# PoE_Injector.net
KiCad netlist of a schematic drawn in Altium Designer
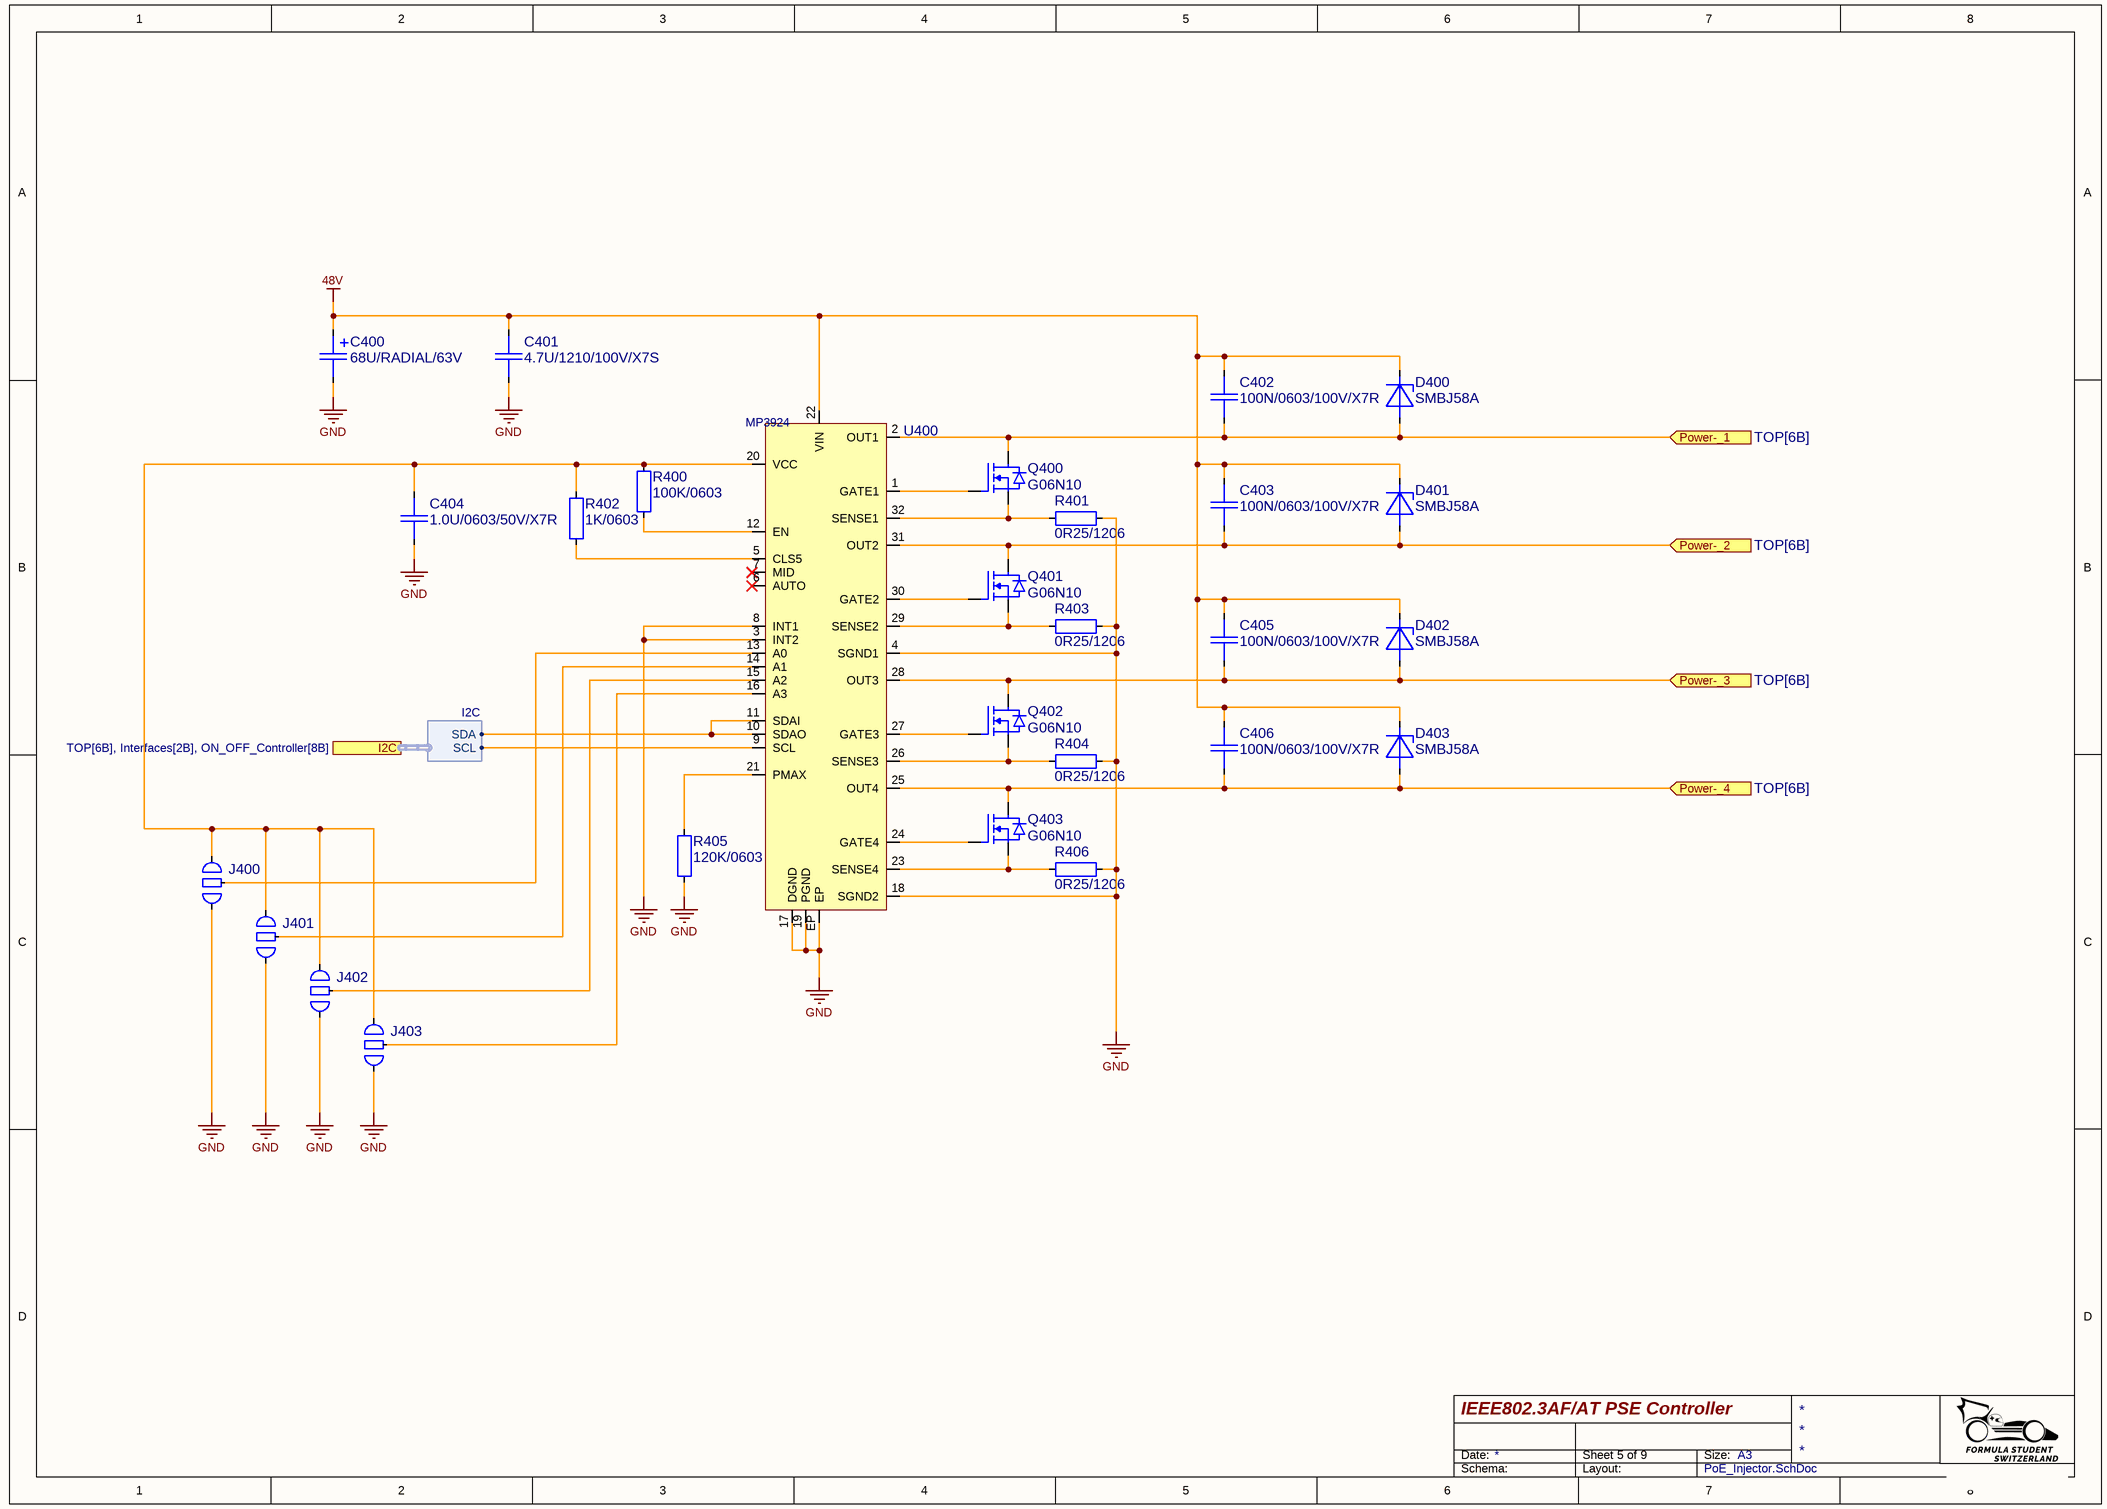
[diagram p0: PoE_Injector.SchDoc]

(export (version "E")
  (design (tool "Eeschema 10.0.6"))
  (components
    (comp (ref "C400")
      (value "68U/RADIAL/63V")
      (footprint "CAP350P80X130")
      (description "CAP THT 8C130 68UF ELKO 63V")
      (fields (field (name "MANUFACTURER") "GENERIC"))
      (libsource (lib "daniw_altium_lib") (part "C_ELEC"))
    )
    (comp (ref "C401")
      (value "4.7U/1210/100V/X7S")
      (footprint "CAP1210_X7R")
      (description "CAP SM 1210 4.7uF 100V X7S")
      (fields (field (name "MANUFACTURER") "GENERIC"))
      (libsource (lib "daniw_altium_lib") (part "C"))
    )
    (comp (ref "C402")
      (value "100N/0603/100V/X7R")
      (footprint "CAP0603_X7R")
      (description "CAP SM 0603 100nF 100V X7R")
      (fields (field (name "MANUFACTURER") "GENERIC"))
      (libsource (lib "daniw_altium_lib") (part "C"))
    )
    (comp (ref "C403")
      (value "100N/0603/100V/X7R")
      (footprint "CAP0603_X7R")
      (description "CAP SM 0603 100nF 100V X7R")
      (fields (field (name "MANUFACTURER") "GENERIC"))
      (libsource (lib "daniw_altium_lib") (part "C"))
    )
    (comp (ref "C404")
      (value "1.0U/0603/50V/X7R")
      (footprint "CAP0603_X7R")
      (description "CAP SM 0603 1.0uF 50V X7R")
      (fields (field (name "MANUFACTURER") "GENERIC"))
      (libsource (lib "daniw_altium_lib") (part "C"))
    )
    (comp (ref "C405")
      (value "100N/0603/100V/X7R")
      (footprint "CAP0603_X7R")
      (description "CAP SM 0603 100nF 100V X7R")
      (fields (field (name "MANUFACTURER") "GENERIC"))
      (libsource (lib "daniw_altium_lib") (part "C"))
    )
    (comp (ref "C406")
      (value "100N/0603/100V/X7R")
      (footprint "CAP0603_X7R")
      (description "CAP SM 0603 100nF 100V X7R")
      (fields (field (name "MANUFACTURER") "GENERIC"))
      (libsource (lib "daniw_altium_lib") (part "C"))
    )
    (comp (ref "D400")
      (value "SMBJ58A")
      (footprint "DIOM5436X265")
      (description "TVS DIODE 58VWM 93.6VC DO214AA")
      (fields (field (name "MANUFACTURER") "Littelfuse Inc."))
      (libsource (lib "daniw_altium_lib") (part "D_Zener"))
    )
    (comp (ref "D401")
      (value "SMBJ58A")
      (footprint "DIOM5436X265")
      (description "TVS DIODE 58VWM 93.6VC DO214AA")
      (fields (field (name "MANUFACTURER") "Littelfuse Inc."))
      (libsource (lib "daniw_altium_lib") (part "D_Zener"))
    )
    (comp (ref "D402")
      (value "SMBJ58A")
      (footprint "DIOM5436X265")
      (description "TVS DIODE 58VWM 93.6VC DO214AA")
      (fields (field (name "MANUFACTURER") "Littelfuse Inc."))
      (libsource (lib "daniw_altium_lib") (part "D_Zener"))
    )
    (comp (ref "D403")
      (value "SMBJ58A")
      (footprint "DIOM5436X265")
      (description "TVS DIODE 58VWM 93.6VC DO214AA")
      (fields (field (name "MANUFACTURER") "Littelfuse Inc."))
      (libsource (lib "daniw_altium_lib") (part "D_Zener"))
    )
    (comp (ref "J400")
      (value "Solder Jumper 3pin 0.2mm")
      (footprint "Solder_Jumper_3pin_0.2mm")
      (description "Solder jumper with three pins with a spacing of 0.2mm")
      (fields (field (name "PART NUMBER") "Solder_Jumper_3pin_0.2mm") (field (name "MANUFACTURER") "NONE"))
      (libsource (lib "daniw_altium_lib") (part "SolderJumper_3"))
    )
    (comp (ref "J401")
      (value "Solder Jumper 3pin 0.2mm")
      (footprint "Solder_Jumper_3pin_0.2mm")
      (description "Solder jumper with three pins with a spacing of 0.2mm")
      (fields (field (name "PART NUMBER") "Solder_Jumper_3pin_0.2mm") (field (name "MANUFACTURER") "NONE"))
      (libsource (lib "daniw_altium_lib") (part "SolderJumper_3"))
    )
    (comp (ref "J402")
      (value "Solder Jumper 3pin 0.2mm")
      (footprint "Solder_Jumper_3pin_0.2mm")
      (description "Solder jumper with three pins with a spacing of 0.2mm")
      (fields (field (name "PART NUMBER") "Solder_Jumper_3pin_0.2mm") (field (name "MANUFACTURER") "NONE"))
      (libsource (lib "daniw_altium_lib") (part "SolderJumper_3"))
    )
    (comp (ref "J403")
      (value "Solder Jumper 3pin 0.2mm")
      (footprint "Solder_Jumper_3pin_0.2mm")
      (description "Solder jumper with three pins with a spacing of 0.2mm")
      (fields (field (name "PART NUMBER") "Solder_Jumper_3pin_0.2mm") (field (name "MANUFACTURER") "NONE"))
      (libsource (lib "daniw_altium_lib") (part "SolderJumper_3"))
    )
    (comp (ref "Q400")
      (value "G06N10")
      (footprint "TO228P990X229-3")
      (description "N100V,RD(MAX)<240M@10V,VTH1.2V~3")
      (fields (field (name "MANUFACTURER") "Goford"))
      (libsource (lib "daniw_altium_lib") (part "MOSFET N_SOT23"))
    )
    (comp (ref "Q401")
      (value "G06N10")
      (footprint "TO228P990X229-3")
      (description "N100V,RD(MAX)<240M@10V,VTH1.2V~3")
      (fields (field (name "MANUFACTURER") "Goford"))
      (libsource (lib "daniw_altium_lib") (part "MOSFET N_SOT23"))
    )
    (comp (ref "Q402")
      (value "G06N10")
      (footprint "TO228P990X229-3")
      (description "N100V,RD(MAX)<240M@10V,VTH1.2V~3")
      (fields (field (name "MANUFACTURER") "Goford"))
      (libsource (lib "daniw_altium_lib") (part "MOSFET N_SOT23"))
    )
    (comp (ref "Q403")
      (value "G06N10")
      (footprint "TO228P990X229-3")
      (description "N100V,RD(MAX)<240M@10V,VTH1.2V~3")
      (fields (field (name "MANUFACTURER") "Goford"))
      (libsource (lib "daniw_altium_lib") (part "MOSFET N_SOT23"))
    )
    (comp (ref "R400")
      (value "100K/0603")
      (footprint "R0603-0.40-WW")
      (description "RES SM 0603 100K")
      (fields (field (name "MANUFACTURER") "GENERIC"))
      (libsource (lib "daniw_altium_lib") (part "R"))
    )
    (comp (ref "R401")
      (value "0R25/1206")
      (footprint "R1206-0.80-WW")
      (description "RES SM 1206 0R25")
      (fields (field (name "MANUFACTURER") "GENERIC"))
      (libsource (lib "daniw_altium_lib") (part "R"))
    )
    (comp (ref "R402")
      (value "1K/0603")
      (footprint "R0603-0.40-WW")
      (description "RES SM 0603 1K")
      (fields (field (name "MANUFACTURER") "GENERIC"))
      (libsource (lib "daniw_altium_lib") (part "R"))
    )
    (comp (ref "R403")
      (value "0R25/1206")
      (footprint "R1206-0.80-WW")
      (description "RES SM 1206 0R25")
      (fields (field (name "MANUFACTURER") "GENERIC"))
      (libsource (lib "daniw_altium_lib") (part "R"))
    )
    (comp (ref "R404")
      (value "0R25/1206")
      (footprint "R1206-0.80-WW")
      (description "RES SM 1206 0R25")
      (fields (field (name "MANUFACTURER") "GENERIC"))
      (libsource (lib "daniw_altium_lib") (part "R"))
    )
    (comp (ref "R405")
      (value "120K/0603")
      (footprint "R0603-0.40-WW")
      (description "RES SM 0603 120K")
      (fields (field (name "MANUFACTURER") "GENERIC"))
      (libsource (lib "daniw_altium_lib") (part "R"))
    )
    (comp (ref "R406")
      (value "0R25/1206")
      (footprint "R1206-0.80-WW")
      (description "RES SM 1206 0R25")
      (fields (field (name "MANUFACTURER") "GENERIC"))
      (libsource (lib "daniw_altium_lib") (part "R"))
    )
    (comp (ref "U400")
      (value "MP3924")
      (footprint "QFN050P500X500X100-32-TH360X360")
      (description "Quad-Port, IEEE 802.3af/at PSE Controller for Power over Ethernet")
      (fields (field (name "MANUFACTURER") "MPS"))
      (libsource (lib "daniw_altium_lib") (part "MP3924"))
    )
  )
  (nets
    (net (code "2") (name "/Power-_1") (class "Default")
      (node (ref "C402") (pin "2") (pinfunction "2_2") (pintype "passive"))
      (node (ref "D400") (pin "2") (pinfunction "2_2") (pintype "passive"))
      (node (ref "Q400") (pin "3") (pinfunction "DRAIN_3") (pintype "passive"))
      (node (ref "U400") (pin "2") (pinfunction "OUT1_2") (pintype "passive"))
    )
    (net (code "3") (name "/Power-_2") (class "Default")
      (node (ref "C403") (pin "2") (pinfunction "2_2") (pintype "passive"))
      (node (ref "D401") (pin "2") (pinfunction "2_2") (pintype "passive"))
      (node (ref "Q401") (pin "3") (pinfunction "DRAIN_3") (pintype "passive"))
      (node (ref "U400") (pin "31") (pinfunction "OUT2_31") (pintype "passive"))
    )
    (net (code "4") (name "/Power-_3") (class "Default")
      (node (ref "C405") (pin "2") (pinfunction "2_2") (pintype "passive"))
      (node (ref "D402") (pin "2") (pinfunction "2_2") (pintype "passive"))
      (node (ref "Q402") (pin "3") (pinfunction "DRAIN_3") (pintype "passive"))
      (node (ref "U400") (pin "28") (pinfunction "OUT3_28") (pintype "passive"))
    )
    (net (code "5") (name "/Power-_4") (class "Default")
      (node (ref "C406") (pin "2") (pinfunction "2_2") (pintype "passive"))
      (node (ref "D403") (pin "2") (pinfunction "2_2") (pintype "passive"))
      (node (ref "Q403") (pin "3") (pinfunction "DRAIN_3") (pintype "passive"))
      (node (ref "U400") (pin "25") (pinfunction "OUT4_25") (pintype "passive"))
    )
    (net (code "6") (name "/SCL") (class "Default")
      (node (ref "U400") (pin "9") (pinfunction "SCL_9") (pintype "passive"))
    )
    (net (code "7") (name "/SDA") (class "Default")
      (node (ref "U400") (pin "10") (pinfunction "SDAO_10") (pintype "passive"))
      (node (ref "U400") (pin "11") (pinfunction "SDAI_11") (pintype "passive"))
    )
    (net (code "9") (name "48V") (class "Default")
      (node (ref "C400") (pin "1") (pinfunction "1_1") (pintype "passive"))
      (node (ref "C401") (pin "1") (pinfunction "1_1") (pintype "passive"))
      (node (ref "C402") (pin "1") (pinfunction "1_1") (pintype "passive"))
      (node (ref "C403") (pin "1") (pinfunction "1_1") (pintype "passive"))
      (node (ref "C405") (pin "1") (pinfunction "1_1") (pintype "passive"))
      (node (ref "C406") (pin "1") (pinfunction "1_1") (pintype "passive"))
      (node (ref "D400") (pin "1") (pinfunction "1_1") (pintype "passive"))
      (node (ref "D401") (pin "1") (pinfunction "1_1") (pintype "passive"))
      (node (ref "D402") (pin "1") (pinfunction "1_1") (pintype "passive"))
      (node (ref "D403") (pin "1") (pinfunction "1_1") (pintype "passive"))
      (node (ref "U400") (pin "22") (pinfunction "VIN_22") (pintype "passive"))
    )
    (net (code "10") (name "GND") (class "Default")
      (node (ref "C400") (pin "2") (pinfunction "2_2") (pintype "passive"))
      (node (ref "C401") (pin "2") (pinfunction "2_2") (pintype "passive"))
      (node (ref "C404") (pin "2") (pinfunction "2_2") (pintype "passive"))
      (node (ref "J400") (pin "1") (pinfunction "1_1") (pintype "passive"))
      (node (ref "J401") (pin "1") (pinfunction "1_1") (pintype "passive"))
      (node (ref "J402") (pin "1") (pinfunction "1_1") (pintype "passive"))
      (node (ref "J403") (pin "1") (pinfunction "1_1") (pintype "passive"))
      (node (ref "R401") (pin "2") (pinfunction "2_2") (pintype "passive"))
      (node (ref "R403") (pin "2") (pinfunction "2_2") (pintype "passive"))
      (node (ref "R404") (pin "2") (pinfunction "2_2") (pintype "passive"))
      (node (ref "R405") (pin "2") (pinfunction "2_2") (pintype "passive"))
      (node (ref "R406") (pin "2") (pinfunction "2_2") (pintype "passive"))
      (node (ref "U400") (pin "17") (pinfunction "DGND_17") (pintype "passive"))
      (node (ref "U400") (pin "18") (pinfunction "SGND2_18") (pintype "passive"))
      (node (ref "U400") (pin "19") (pinfunction "PGND_19") (pintype "passive"))
      (node (ref "U400") (pin "3") (pinfunction "INT2_3") (pintype "passive"))
      (node (ref "U400") (pin "4") (pinfunction "SGND1_4") (pintype "passive"))
      (node (ref "U400") (pin "8") (pinfunction "INT1_8") (pintype "passive"))
      (node (ref "U400") (pin "EP") (pinfunction "EP_EP") (pintype "passive"))
    )
    (net (code "11") (name "Net-(Q400-GATE)") (class "Default")
      (node (ref "Q400") (pin "1") (pinfunction "GATE_1") (pintype "passive"))
      (node (ref "U400") (pin "1") (pinfunction "GATE1_1") (pintype "passive"))
    )
    (net (code "12") (name "Net-(Q400-SOURCE)") (class "Default")
      (node (ref "Q400") (pin "2") (pinfunction "SOURCE_2") (pintype "passive"))
      (node (ref "R401") (pin "1") (pinfunction "1_1") (pintype "passive"))
      (node (ref "U400") (pin "32") (pinfunction "SENSE1_32") (pintype "passive"))
    )
    (net (code "13") (name "Net-(Q401-GATE)") (class "Default")
      (node (ref "Q401") (pin "1") (pinfunction "GATE_1") (pintype "passive"))
      (node (ref "U400") (pin "30") (pinfunction "GATE2_30") (pintype "passive"))
    )
    (net (code "14") (name "Net-(Q401-SOURCE)") (class "Default")
      (node (ref "Q401") (pin "2") (pinfunction "SOURCE_2") (pintype "passive"))
      (node (ref "R403") (pin "1") (pinfunction "1_1") (pintype "passive"))
      (node (ref "U400") (pin "29") (pinfunction "SENSE2_29") (pintype "passive"))
    )
    (net (code "15") (name "Net-(Q402-GATE)") (class "Default")
      (node (ref "Q402") (pin "1") (pinfunction "GATE_1") (pintype "passive"))
      (node (ref "U400") (pin "27") (pinfunction "GATE3_27") (pintype "passive"))
    )
    (net (code "16") (name "Net-(Q402-SOURCE)") (class "Default")
      (node (ref "Q402") (pin "2") (pinfunction "SOURCE_2") (pintype "passive"))
      (node (ref "R404") (pin "1") (pinfunction "1_1") (pintype "passive"))
      (node (ref "U400") (pin "26") (pinfunction "SENSE3_26") (pintype "passive"))
    )
    (net (code "17") (name "Net-(Q403-GATE)") (class "Default")
      (node (ref "Q403") (pin "1") (pinfunction "GATE_1") (pintype "passive"))
      (node (ref "U400") (pin "24") (pinfunction "GATE4_24") (pintype "passive"))
    )
    (net (code "18") (name "Net-(Q403-SOURCE)") (class "Default")
      (node (ref "Q403") (pin "2") (pinfunction "SOURCE_2") (pintype "passive"))
      (node (ref "R406") (pin "1") (pinfunction "1_1") (pintype "passive"))
      (node (ref "U400") (pin "23") (pinfunction "SENSE4_23") (pintype "passive"))
    )
    (net (code "19") (name "Net-(U400-A0)") (class "Default")
      (node (ref "J400") (pin "2") (pinfunction "2_2") (pintype "passive"))
      (node (ref "U400") (pin "13") (pinfunction "A0_13") (pintype "passive"))
    )
    (net (code "20") (name "Net-(U400-A1)") (class "Default")
      (node (ref "J401") (pin "2") (pinfunction "2_2") (pintype "passive"))
      (node (ref "U400") (pin "14") (pinfunction "A1_14") (pintype "passive"))
    )
    (net (code "21") (name "Net-(U400-A2)") (class "Default")
      (node (ref "J402") (pin "2") (pinfunction "2_2") (pintype "passive"))
      (node (ref "U400") (pin "15") (pinfunction "A2_15") (pintype "passive"))
    )
    (net (code "22") (name "Net-(U400-A3)") (class "Default")
      (node (ref "J403") (pin "2") (pinfunction "2_2") (pintype "passive"))
      (node (ref "U400") (pin "16") (pinfunction "A3_16") (pintype "passive"))
    )
    (net (code "23") (name "Net-(U400-CLS5)") (class "Default")
      (node (ref "R402") (pin "2") (pinfunction "2_2") (pintype "passive"))
      (node (ref "U400") (pin "5") (pinfunction "CLS5_5") (pintype "passive"))
    )
    (net (code "24") (name "Net-(U400-EN)") (class "Default")
      (node (ref "R400") (pin "2") (pinfunction "2_2") (pintype "passive"))
      (node (ref "U400") (pin "12") (pinfunction "EN_12") (pintype "passive"))
    )
    (net (code "25") (name "Net-(U400-PMAX)") (class "Default")
      (node (ref "R405") (pin "1") (pinfunction "1_1") (pintype "passive"))
      (node (ref "U400") (pin "21") (pinfunction "PMAX_21") (pintype "passive"))
    )
    (net (code "26") (name "Net-(U400-VCC)") (class "Default")
      (node (ref "C404") (pin "1") (pinfunction "1_1") (pintype "passive"))
      (node (ref "J400") (pin "3") (pinfunction "3_3") (pintype "passive"))
      (node (ref "J401") (pin "3") (pinfunction "3_3") (pintype "passive"))
      (node (ref "J402") (pin "3") (pinfunction "3_3") (pintype "passive"))
      (node (ref "J403") (pin "3") (pinfunction "3_3") (pintype "passive"))
      (node (ref "R400") (pin "1") (pinfunction "1_1") (pintype "passive"))
      (node (ref "R402") (pin "1") (pinfunction "1_1") (pintype "passive"))
      (node (ref "U400") (pin "20") (pinfunction "VCC_20") (pintype "passive"))
    )
    (net (code "27") (name "unconnected-(U400-AUTO-Pad6)") (class "Default")
      (node (ref "U400") (pin "6") (pinfunction "AUTO_6") (pintype "passive+no_connect"))
    )
    (net (code "28") (name "unconnected-(U400-MID-Pad7)") (class "Default")
      (node (ref "U400") (pin "7") (pinfunction "MID_7") (pintype "passive+no_connect"))
    )
  )
)
